# ProProject_PetCareSTM32_MiniSTM32_2024-0.net
KiCad netlist of a schematic drawn in EasyEDA Pro
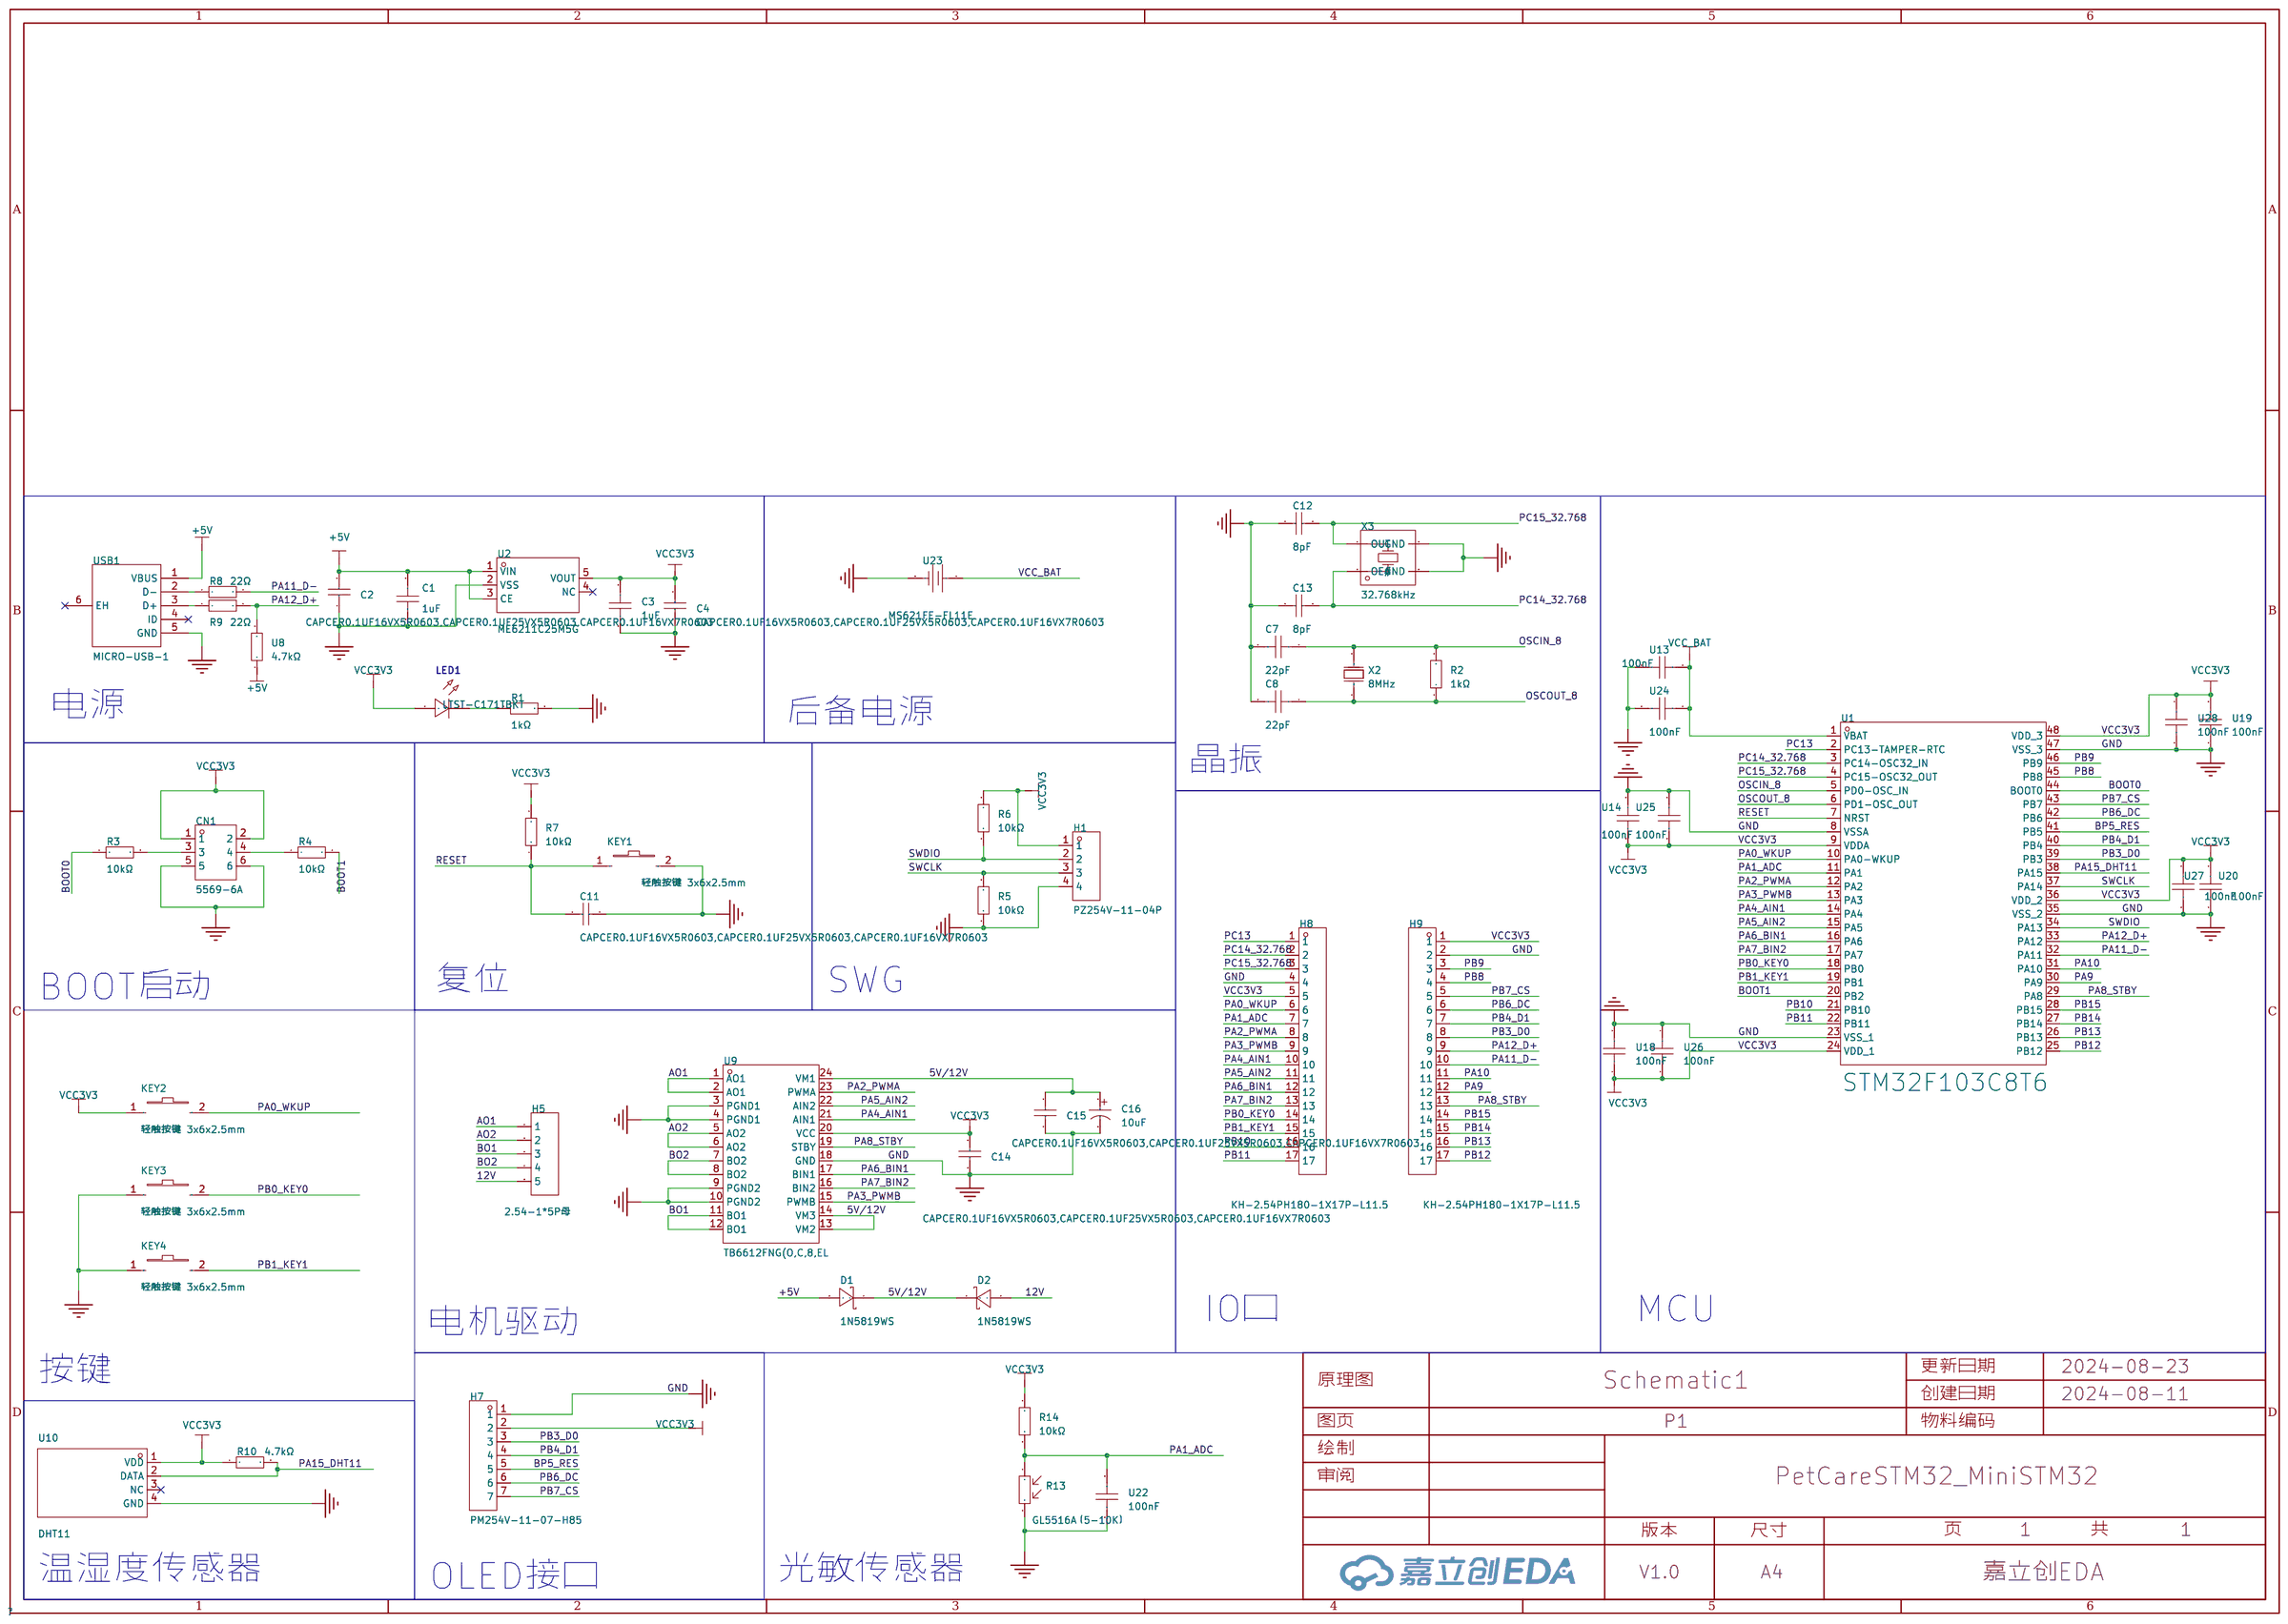
[diagram p0: schematic sheet]

(export (version "E")
  (design (tool "Eeschema 10.0.6"))
  (components
    (comp (ref "C1")
      (value "1uF")
      (footprint "easyedapro:C0603")
      (description "容值:1uF;精度:±10%;额定电压:50V;材质(温度系数):X5R;")
      (fields
        (field (name "Manufacturer Part") "CL10A105KB8NNNC")
        (field (name "Manufacturer") "SAMSUNG(三星)")
      )
      (libsource (lib "easyedapro") (part "CL10A105KB8NNNC"))
    )
    (comp (ref "C2")
      (value "CAPCER0.1UF16VX5R0603,CAPCER0.1UF25VX5R0603,CAPCER0.1UF16VX7R0603")
      (footprint "easyedapro:C0603")
      (libsource (lib "easyedapro") (part "CAPCER0.1UF16VX5R0603,CAPCER0.1UF25VX5R0603,CAPCER0.1UF16VX7R0603"))
    )
    (comp (ref "C3")
      (value "1uF")
      (footprint "easyedapro:C0603")
      (description "容值:1uF;精度:±10%;额定电压:50V;材质(温度系数):X5R;")
      (fields
        (field (name "Manufacturer Part") "CL10A105KB8NNNC")
        (field (name "Manufacturer") "SAMSUNG(三星)")
      )
      (libsource (lib "easyedapro") (part "CL10A105KB8NNNC"))
    )
    (comp (ref "C4")
      (value "CAPCER0.1UF16VX5R0603,CAPCER0.1UF25VX5R0603,CAPCER0.1UF16VX7R0603")
      (footprint "easyedapro:C0603")
      (libsource (lib "easyedapro") (part "CAPCER0.1UF16VX5R0603,CAPCER0.1UF25VX5R0603,CAPCER0.1UF16VX7R0603"))
    )
    (comp (ref "C7")
      (value "22pF")
      (footprint "easyedapro:C0603")
      (description "容值:22pF;精度:±5%;额定电压:50V;材质(温度系数):C0G;")
      (fields
        (field (name "Manufacturer Part") "CL10C220JB81PNC")
        (field (name "Manufacturer") "SAMSUNG(三星)")
      )
      (libsource (lib "easyedapro") (part "CL10C220JB81PNC"))
    )
    (comp (ref "C8")
      (value "22pF")
      (footprint "easyedapro:C0603")
      (description "容值:22pF;精度:±5%;额定电压:50V;材质(温度系数):C0G;")
      (fields
        (field (name "Manufacturer Part") "CL10C220JB81PNC")
        (field (name "Manufacturer") "SAMSUNG(三星)")
      )
      (libsource (lib "easyedapro") (part "CL10C220JB81PNC"))
    )
    (comp (ref "C11")
      (value "CAPCER0.1UF16VX5R0603,CAPCER0.1UF25VX5R0603,CAPCER0.1UF16VX7R0603")
      (footprint "easyedapro:C0603")
      (libsource (lib "easyedapro") (part "CAPCER0.1UF16VX5R0603,CAPCER0.1UF25VX5R0603,CAPCER0.1UF16VX7R0603"))
    )
    (comp (ref "C12")
      (value "8pF")
      (footprint "easyedapro:C0603")
      (description "容值:8pF;额定电压:50V;材质(温度系数):C0G;")
      (fields (field (name "Manufacturer Part") "0603CG8R0C500NT") (field (name "Manufacturer") "FH(风华)"))
      (libsource (lib "easyedapro") (part "0603CG8R0C500NT_C36508"))
    )
    (comp (ref "C13")
      (value "8pF")
      (footprint "easyedapro:C0603")
      (description "容值:8pF;额定电压:50V;材质(温度系数):C0G;")
      (fields (field (name "Manufacturer Part") "0603CG8R0C500NT") (field (name "Manufacturer") "FH(风华)"))
      (libsource (lib "easyedapro") (part "0603CG8R0C500NT_C36508"))
    )
    (comp (ref "C14")
      (value "CAPCER0.1UF16VX5R0603,CAPCER0.1UF25VX5R0603,CAPCER0.1UF16VX7R0603")
      (footprint "easyedapro:C0603")
      (libsource (lib "easyedapro") (part "CAPCER0.1UF16VX5R0603,CAPCER0.1UF25VX5R0603,CAPCER0.1UF16VX7R0603"))
    )
    (comp (ref "C15")
      (value "CAPCER0.1UF16VX5R0603,CAPCER0.1UF25VX5R0603,CAPCER0.1UF16VX7R0603")
      (footprint "easyedapro:C0603")
      (libsource (lib "easyedapro") (part "CAPCER0.1UF16VX5R0603,CAPCER0.1UF25VX5R0603,CAPCER0.1UF16VX7R0603"))
    )
    (comp (ref "C16")
      (value "10uF")
      (footprint "easyedapro:CAP-TH_BD5.0-P2.00-D0.8-FD")
      (description "容值:10uF;精度:±20%;额定电压:25V;")
      (fields (field (name "Manufacturer Part") "KF100M025C110A") (field (name "Manufacturer") "CapXon(丰宾)"))
      (libsource (lib "easyedapro") (part "KF100M025C110A"))
    )
    (comp (ref "CN1")
      (value "5569-6A")
      (footprint "easyedapro:CONN-TH_6P-P4.20_5569-6A-1")
      (libsource (lib "easyedapro") (part "5569-6A"))
    )
    (comp (ref "D1")
      (value "1N5819WS")
      (footprint "easyedapro:SOD-323_L1.8-W1.3-LS2.5-RD")
      (description "正向压降(Vf):600mV@1A;直流反向耐压(Vr):40V;平均整流电流(Io):1A;")
      (fields (field (name "Manufacturer") "Hottech(合科泰)"))
      (libsource (lib "easyedapro") (part "1N5819WS"))
    )
    (comp (ref "D2")
      (value "1N5819WS")
      (footprint "easyedapro:SOD-323_L1.8-W1.3-LS2.5-RD")
      (description "正向压降(Vf):600mV@1A;直流反向耐压(Vr):40V;平均整流电流(Io):1A;")
      (fields (field (name "Manufacturer") "Hottech(合科泰)"))
      (libsource (lib "easyedapro") (part "1N5819WS"))
    )
    (comp (ref "H1")
      (value "PZ254V-11-04P")
      (footprint "easyedapro:HDR-TH_4P-P2.54-V-M")
      (fields (field (name "Manufacturer") "XFCN(兴飞)"))
      (libsource (lib "easyedapro") (part "PZ254V-11-04P_C2691448"))
    )
    (comp (ref "H5")
      (value "2.54-1*5P母")
      (footprint "easyedapro:HDR-TH_5P-P2.54-V-F")
      (description "插孔结构:1x5P;间距:2.54mm;行距:-;安装类型:直插;排数:单排;总孔位数:5P;塑高:-;触头材质:-;触头镀层:-;")
      (fields (field (name "Manufacturer") "BOOMELE(博穆精密)"))
      (libsource (lib "easyedapro") (part "Header-Female-2.54_1x5"))
    )
    (comp (ref "H7")
      (value "PM254V-11-07-H85")
      (footprint "easyedapro:HDR-TH_7P-P2.54-V-F")
      (fields (field (name "Manufacturer") "XFCN(兴飞)"))
      (libsource (lib "easyedapro") (part "PM254V-11-07-H85"))
    )
    (comp (ref "H8")
      (value "KH-2.54PH180-1X17P-L11.5")
      (footprint "easyedapro:HDR-TH_17P-P2.54-V-M")
      (fields (field (name "Manufacturer") "kinghelm(金航标)"))
      (libsource (lib "easyedapro") (part "KH-2.54PH180-1X17P-L11.5"))
    )
    (comp (ref "H9")
      (value "KH-2.54PH180-1X17P-L11.5")
      (footprint "easyedapro:HDR-TH_17P-P2.54-V-M")
      (fields (field (name "Manufacturer") "kinghelm(金航标)"))
      (libsource (lib "easyedapro") (part "KH-2.54PH180-1X17P-L11.5"))
    )
    (comp (ref "KEY1")
      (value "轻触按键 3x6x2.5mm")
      (footprint "easyedapro:SW-SMD_L6.0-W3.6-LS8.0")
      (libsource (lib "easyedapro") (part "3x6x2.5mm"))
    )
    (comp (ref "KEY2")
      (value "轻触按键 3x6x2.5mm")
      (footprint "easyedapro:SW-SMD_L6.0-W3.6-LS8.0")
      (libsource (lib "easyedapro") (part "3x6x2.5mm"))
    )
    (comp (ref "KEY3")
      (value "轻触按键 3x6x2.5mm")
      (footprint "easyedapro:SW-SMD_L6.0-W3.6-LS8.0")
      (libsource (lib "easyedapro") (part "3x6x2.5mm"))
    )
    (comp (ref "KEY4")
      (value "轻触按键 3x6x2.5mm")
      (footprint "easyedapro:SW-SMD_L6.0-W3.6-LS8.0")
      (libsource (lib "easyedapro") (part "3x6x2.5mm"))
    )
    (comp (ref "LED1")
      (value "LTST-C171TBKT")
      (footprint "easyedapro:LED_0805")
      (fields (field (name "Manufacturer") "LITEON(光宝)"))
      (libsource (lib "easyedapro") (part "LED_B"))
    )
    (comp (ref "R1")
      (value "1kΩ")
      (footprint "easyedapro:R0603")
      (description "电阻类型:厚膜电阻;阻值:1kΩ;精度:±1%;功率:100mW;最大工作电压:75V;温度系数:±100ppm/°C;")
      (fields (field (name "Manufacturer Part") "RC0603FR-071KL") (field (name "Manufacturer") "YAGEO(国巨)"))
      (libsource (lib "easyedapro") (part "RC0603FR-071KL"))
    )
    (comp (ref "R2")
      (value "1kΩ")
      (footprint "easyedapro:R0603")
      (description "电阻类型:厚膜电阻;阻值:1kΩ;精度:±0.5%;功率:100mW;最大工作电压:75V;温度系数:±100ppm/°C;")
      (fields
        (field (name "Manufacturer Part") "0603WAD1001T5E")
        (field (name "Manufacturer") "UNI-ROYAL(厚声)")
      )
      (libsource (lib "easyedapro") (part "0603WAD1001T5E"))
    )
    (comp (ref "R3")
      (value "10kΩ")
      (footprint "easyedapro:R0603")
      (description "电阻类型:厚膜电阻;阻值:10kΩ;精度:±1%;功率:100mW;最大工作电压:75V;温度系数:±100ppm/°C;")
      (fields
        (field (name "Manufacturer Part") "0603WAF1002T5E")
        (field (name "Manufacturer") "UNI-ROYAL(厚声)")
      )
      (libsource (lib "easyedapro") (part "0603WAF1002T5E"))
    )
    (comp (ref "R4")
      (value "10kΩ")
      (footprint "easyedapro:R0603")
      (description "电阻类型:厚膜电阻;阻值:10kΩ;精度:±1%;功率:100mW;最大工作电压:75V;温度系数:±100ppm/°C;")
      (fields
        (field (name "Manufacturer Part") "0603WAF1002T5E")
        (field (name "Manufacturer") "UNI-ROYAL(厚声)")
      )
      (libsource (lib "easyedapro") (part "0603WAF1002T5E"))
    )
    (comp (ref "R5")
      (value "10kΩ")
      (footprint "easyedapro:R0603")
      (description "电阻类型:厚膜电阻;阻值:10kΩ;精度:±1%;功率:100mW;最大工作电压:75V;温度系数:±100ppm/°C;")
      (fields
        (field (name "Manufacturer Part") "0603WAF1002T5E")
        (field (name "Manufacturer") "UNI-ROYAL(厚声)")
      )
      (libsource (lib "easyedapro") (part "0603WAF1002T5E"))
    )
    (comp (ref "R6")
      (value "10kΩ")
      (footprint "easyedapro:R0603")
      (description "电阻类型:厚膜电阻;阻值:10kΩ;精度:±1%;功率:100mW;最大工作电压:75V;温度系数:±100ppm/°C;")
      (fields
        (field (name "Manufacturer Part") "0603WAF1002T5E")
        (field (name "Manufacturer") "UNI-ROYAL(厚声)")
      )
      (libsource (lib "easyedapro") (part "0603WAF1002T5E"))
    )
    (comp (ref "R7")
      (value "10kΩ")
      (footprint "easyedapro:R0603")
      (description "电阻类型:厚膜电阻;阻值:10kΩ;精度:±1%;功率:100mW;最大工作电压:75V;温度系数:±100ppm/°C;")
      (fields
        (field (name "Manufacturer Part") "0603WAF1002T5E")
        (field (name "Manufacturer") "UNI-ROYAL(厚声)")
      )
      (libsource (lib "easyedapro") (part "0603WAF1002T5E"))
    )
    (comp (ref "R8")
      (value "22Ω")
      (footprint "easyedapro:R0805")
      (description "电阻类型:薄膜电阻;阻值:22Ω;精度:±1%;功率:250mW;最大工作电压:150V;温度系数:±25ppm/°C;")
      (fields
        (field (name "Manufacturer Part") "TC0525F220JT5E")
        (field (name "Manufacturer") "UNI-ROYAL(厚声)")
      )
      (libsource (lib "easyedapro") (part "TC0525F220JT5E"))
    )
    (comp (ref "R9")
      (value "22Ω")
      (footprint "easyedapro:R0805")
      (description "电阻类型:薄膜电阻;阻值:22Ω;精度:±1%;功率:250mW;最大工作电压:150V;温度系数:±25ppm/°C;")
      (fields
        (field (name "Manufacturer Part") "TC0525F220JT5E")
        (field (name "Manufacturer") "UNI-ROYAL(厚声)")
      )
      (libsource (lib "easyedapro") (part "TC0525F220JT5E"))
    )
    (comp (ref "R10")
      (value "4.7kΩ")
      (footprint "easyedapro:R1206")
      (description "电阻类型:厚膜电阻;阻值:4.7kΩ;精度:±1%;功率:250mW;最大工作电压:200V;温度系数:±100ppm/°C;")
      (fields
        (field (name "Manufacturer Part") "1206W4F4701T5E")
        (field (name "Manufacturer") "UNI-ROYAL(厚声)")
      )
      (libsource (lib "easyedapro") (part "1206W4F4701T5E"))
    )
    (comp (ref "R13")
      (value "GL5516A（5-10K）")
      (footprint "easyedapro:RES-TH_L5.1-W4.3-P3.40_GL55")
      (description "暗电阻:200kΩ;亮电阻 @ 10Lux:5kΩ~10kΩ;光谱峰值(波长):540nm;")
      (fields (field (name "Manufacturer") "JCHL(晶创和立)"))
      (libsource (lib "easyedapro") (part "GL5516A(5-10K)"))
    )
    (comp (ref "R14")
      (value "10kΩ")
      (footprint "easyedapro:R0603")
      (description "电阻类型:厚膜电阻;阻值:10kΩ;精度:±1%;功率:100mW;最大工作电压:75V;温度系数:±100ppm/°C;")
      (fields
        (field (name "Manufacturer Part") "0603WAF1002T5E")
        (field (name "Manufacturer") "UNI-ROYAL(厚声)")
      )
      (libsource (lib "easyedapro") (part "0603WAF1002T5E"))
    )
    (comp (ref "U1")
      (value "STM32F103C8T6")
      (footprint "easyedapro:LQFP-48_L7.0-W7.0-P0.50-LS9.0-BL")
      (description "CPU内核:ARM-M3;程序存储容量:64KB;RAM总容量:20KB;GPIO端口数量:37;工作电压范围:2V~3.6V;CPU最大主频:72MHz;程序存储器类型:FLASH;")
      (fields (field (name "Manufacturer") "ST(意法半导体)"))
      (libsource (lib "easyedapro") (part "STM32F103C8T6"))
    )
    (comp (ref "U2")
      (value "ME6211C25M5G")
      (footprint "easyedapro:SOT-23-5_L2.9-W1.7-P0.95-LS2.8-BL")
      (fields (field (name "Manufacturer") "MICRONE(南京微盟)"))
      (libsource (lib "easyedapro") (part "ME6211C25M5G"))
    )
    (comp (ref "U8")
      (value "4.7kΩ")
      (footprint "easyedapro:R0603")
      (description "电阻类型:薄膜电阻;阻值:4.7kΩ;精度:±1%;功率:100mW;最大工作电压:75V;温度系数:±50ppm/°C;")
      (fields (field (name "Manufacturer Part") "AR03FTDX4701A") (field (name "Manufacturer") "Viking(光颉)"))
      (libsource (lib "easyedapro") (part "AR03FTDX4701A"))
    )
    (comp (ref "U9")
      (value "TB6612FNG(O,C,8,EL")
      (footprint "easyedapro:SSOP-24_L8.4-W5.8-P0.65-LS7.8-BL")
      (description "双直流电机驱动器集成电路")
      (fields (field (name "Manufacturer") "TOSHIBA(东芝)"))
      (libsource (lib "easyedapro") (part "TB6612FNG(O,C,8,EL"))
    )
    (comp (ref "U10")
      (value "DHT11")
      (footprint "easyedapro:SENSOR-TH_DHT11")
      (description "新款电容式数字温湿度传感器,老款已停产16.1x12.6x5.8mm")
      (fields (field (name "Manufacturer") "广州奥松"))
      (libsource (lib "easyedapro") (part "DHT11"))
    )
    (comp (ref "U13")
      (value "100nF")
      (footprint "easyedapro:C0603")
      (description "容值:100nF;精度:±10%;额定电压:50V;材质(温度系数):X7R;")
      (fields
        (field (name "Manufacturer Part") "CGA0603X7R104K500JT")
        (field (name "Manufacturer") "HRE(芯声)")
      )
      (libsource (lib "easyedapro") (part "CGA0603X7R104K500JT"))
    )
    (comp (ref "U14")
      (value "100nF")
      (footprint "easyedapro:C0603")
      (description "容值:100nF;精度:±10%;额定电压:50V;材质(温度系数):X7R;")
      (fields
        (field (name "Manufacturer Part") "CGA0603X7R104K500JT")
        (field (name "Manufacturer") "HRE(芯声)")
      )
      (libsource (lib "easyedapro") (part "CGA0603X7R104K500JT"))
    )
    (comp (ref "U18")
      (value "100nF")
      (footprint "easyedapro:C0603")
      (description "容值:100nF;精度:±10%;额定电压:50V;材质(温度系数):X7R;")
      (fields
        (field (name "Manufacturer Part") "CGA0603X7R104K500JT")
        (field (name "Manufacturer") "HRE(芯声)")
      )
      (libsource (lib "easyedapro") (part "CGA0603X7R104K500JT"))
    )
    (comp (ref "U19")
      (value "100nF")
      (footprint "easyedapro:C0603")
      (description "容值:100nF;精度:±10%;额定电压:50V;材质(温度系数):X7R;")
      (fields
        (field (name "Manufacturer Part") "CGA0603X7R104K500JT")
        (field (name "Manufacturer") "HRE(芯声)")
      )
      (libsource (lib "easyedapro") (part "CGA0603X7R104K500JT"))
    )
    (comp (ref "U20")
      (value "100nF")
      (footprint "easyedapro:C0603")
      (description "容值:100nF;精度:±10%;额定电压:50V;材质(温度系数):X7R;")
      (fields
        (field (name "Manufacturer Part") "CGA0603X7R104K500JT")
        (field (name "Manufacturer") "HRE(芯声)")
      )
      (libsource (lib "easyedapro") (part "CGA0603X7R104K500JT"))
    )
    (comp (ref "U22")
      (value "100nF")
      (footprint "easyedapro:C0603")
      (description "容值:100nF;精度:±10%;额定电压:50V;材质(温度系数):X7R;")
      (fields
        (field (name "Manufacturer Part") "CGA0603X7R104K500JT")
        (field (name "Manufacturer") "HRE(芯声)")
      )
      (libsource (lib "easyedapro") (part "CGA0603X7R104K500JT"))
    )
    (comp (ref "U23")
      (value "MS621FE-FL11E")
      (footprint "easyedapro:BAT-SMD_FL11E")
      (description "FL11E 3.3V可充电纽扣电池 5.5mAH")
      (fields (field (name "Manufacturer") "Seiko(精工)"))
      (libsource (lib "easyedapro") (part "MS621FE-FL11E"))
    )
    (comp (ref "U24")
      (value "100nF")
      (footprint "easyedapro:C0603")
      (description "容值:100nF;精度:±10%;额定电压:50V;材质(温度系数):X7R;")
      (fields
        (field (name "Manufacturer Part") "CGA0603X7R104K500JT")
        (field (name "Manufacturer") "HRE(芯声)")
      )
      (libsource (lib "easyedapro") (part "CGA0603X7R104K500JT"))
    )
    (comp (ref "U25")
      (value "100nF")
      (footprint "easyedapro:C0603")
      (description "容值:100nF;精度:±10%;额定电压:50V;材质(温度系数):X7R;")
      (fields
        (field (name "Manufacturer Part") "CGA0603X7R104K500JT")
        (field (name "Manufacturer") "HRE(芯声)")
      )
      (libsource (lib "easyedapro") (part "CGA0603X7R104K500JT"))
    )
    (comp (ref "U26")
      (value "100nF")
      (footprint "easyedapro:C0603")
      (description "容值:100nF;精度:±10%;额定电压:50V;材质(温度系数):X7R;")
      (fields
        (field (name "Manufacturer Part") "CGA0603X7R104K500JT")
        (field (name "Manufacturer") "HRE(芯声)")
      )
      (libsource (lib "easyedapro") (part "CGA0603X7R104K500JT"))
    )
    (comp (ref "U27")
      (value "100nF")
      (footprint "easyedapro:C0603")
      (description "容值:100nF;精度:±10%;额定电压:50V;材质(温度系数):X7R;")
      (fields
        (field (name "Manufacturer Part") "CGA0603X7R104K500JT")
        (field (name "Manufacturer") "HRE(芯声)")
      )
      (libsource (lib "easyedapro") (part "CGA0603X7R104K500JT"))
    )
    (comp (ref "U28")
      (value "100nF")
      (footprint "easyedapro:C0603")
      (description "容值:100nF;精度:±10%;额定电压:50V;材质(温度系数):X7R;")
      (fields
        (field (name "Manufacturer Part") "CGA0603X7R104K500JT")
        (field (name "Manufacturer") "HRE(芯声)")
      )
      (libsource (lib "easyedapro") (part "CGA0603X7R104K500JT"))
    )
    (comp (ref "USB1")
      (value "MICRO-USB-1")
      (footprint "easyedapro:MICRO-USB-SMD_C9900008946")
      (libsource (lib "easyedapro") (part "MICRO-USB-1"))
    )
    (comp (ref "X2")
      (value "8MHz")
      (footprint "easyedapro:OSC-SMD_L5.0-W3.2")
      (description "晶振类型:贴片晶振;频率:8MHz;常温频差:±20ppm;外接负载电容:18pF;频率稳定度(全温):±30ppm;")
      (fields
        (field (name "Manufacturer Part") "ABM3-8.000MHZ-D2Y-T")
        (field (name "Manufacturer") "ABRACON")
      )
      (libsource (lib "easyedapro") (part "ABM3-8.000MHZ-D2Y-T"))
    )
    (comp (ref "X3")
      (value "32.768kHz")
      (footprint "easyedapro:CRYSTAL-SMD_4P-L8.0-W3.8-BL")
      (description "晶振类型:-;频率:32.768kHz;常温频差:±20ppm;外接负载电容:12.5pF;频率稳定度(全温):-;")
      (fields (field (name "Manufacturer Part") "ABS25-32.768KHZ-T") (field (name "Manufacturer") "ABRACON"))
      (libsource (lib "easyedapro") (part "ABS25-32.768KHZ-T"))
    )
  )
  (nets
    (net (code "1") (name "+5V") (class "Default")
      (node (ref "C1") (pin "2") (pinfunction "2_2") (pintype "unspecified"))
      (node (ref "C2") (pin "2") (pinfunction "2_2") (pintype "input"))
      (node (ref "D1") (pin "2") (pinfunction "A_2") (pintype "unspecified"))
      (node (ref "U2") (pin "1") (pinfunction "VIN_1") (pintype "unspecified"))
      (node (ref "U2") (pin "3") (pinfunction "CE_3") (pintype "unspecified"))
      (node (ref "U8") (pin "1") (pinfunction "1_1") (pintype "unspecified"))
      (node (ref "USB1") (pin "1") (pinfunction "VBUS_1") (pintype "input"))
    )
    (net (code "2") (name "/5V{slash}12V") (class "Default")
      (node (ref "C15") (pin "2") (pinfunction "2_2") (pintype "input"))
      (node (ref "C16") (pin "1") (pinfunction "1_1") (pintype "input"))
      (node (ref "D1") (pin "1") (pinfunction "K_1") (pintype "unspecified"))
      (node (ref "D2") (pin "1") (pinfunction "K_1") (pintype "unspecified"))
      (node (ref "U9") (pin "13") (pinfunction "VM2_13") (pintype "unspecified"))
      (node (ref "U9") (pin "14") (pinfunction "VM3_14") (pintype "unspecified"))
      (node (ref "U9") (pin "24") (pinfunction "VM1_24") (pintype "unspecified"))
    )
    (net (code "3") (name "/12V") (class "Default")
      (node (ref "D2") (pin "2") (pinfunction "A_2") (pintype "unspecified"))
      (node (ref "H5") (pin "5") (pinfunction "5_5") (pintype "input"))
    )
    (net (code "4") (name "/AO1") (class "Default")
      (node (ref "H5") (pin "1") (pinfunction "1_1") (pintype "input"))
      (node (ref "U9") (pin "1") (pinfunction "AO1_1") (pintype "unspecified"))
      (node (ref "U9") (pin "2") (pinfunction "AO1_2") (pintype "unspecified"))
    )
    (net (code "5") (name "/AO2") (class "Default")
      (node (ref "H5") (pin "2") (pinfunction "2_2") (pintype "input"))
      (node (ref "U9") (pin "5") (pinfunction "AO2_5") (pintype "unspecified"))
      (node (ref "U9") (pin "6") (pinfunction "AO2_6") (pintype "unspecified"))
    )
    (net (code "6") (name "/BO1") (class "Default")
      (node (ref "H5") (pin "3") (pinfunction "3_3") (pintype "input"))
      (node (ref "U9") (pin "11") (pinfunction "BO1_11") (pintype "unspecified"))
      (node (ref "U9") (pin "12") (pinfunction "BO1_12") (pintype "unspecified"))
    )
    (net (code "7") (name "/BO2") (class "Default")
      (node (ref "H5") (pin "4") (pinfunction "4_4") (pintype "input"))
      (node (ref "U9") (pin "7") (pinfunction "BO2_7") (pintype "unspecified"))
      (node (ref "U9") (pin "8") (pinfunction "BO2_8") (pintype "unspecified"))
    )
    (net (code "8") (name "/BOOT0") (class "Default")
      (node (ref "R3") (pin "1") (pinfunction "1_1") (pintype "input"))
      (node (ref "U1") (pin "44") (pinfunction "BOOT0_44") (pintype "unspecified"))
    )
    (net (code "9") (name "/BOOT1") (class "Default")
      (node (ref "R4") (pin "2") (pinfunction "2_2") (pintype "input"))
      (node (ref "U1") (pin "20") (pinfunction "PB2_20") (pintype "unspecified"))
    )
    (net (code "10") (name "/BP5_RES") (class "Default")
      (node (ref "H7") (pin "5") (pinfunction "5_5") (pintype "unspecified"))
      (node (ref "U1") (pin "41") (pinfunction "PB5_41") (pintype "unspecified"))
    )
    (net (code "11") (name "/OSCIN_8") (class "Default")
      (node (ref "C7") (pin "1") (pinfunction "1_1") (pintype "unspecified"))
      (node (ref "R2") (pin "2") (pinfunction "2_2") (pintype "input"))
      (node (ref "U1") (pin "5") (pinfunction "PD0-OSC_IN_5") (pintype "unspecified"))
      (node (ref "X2") (pin "2") (pinfunction "OSC2_2") (pintype "input"))
    )
    (net (code "12") (name "/OSCOUT_8") (class "Default")
      (node (ref "C8") (pin "1") (pinfunction "1_1") (pintype "unspecified"))
      (node (ref "R2") (pin "1") (pinfunction "1_1") (pintype "input"))
      (node (ref "U1") (pin "6") (pinfunction "PD1-OSC_OUT_6") (pintype "unspecified"))
      (node (ref "X2") (pin "1") (pinfunction "OSC1_1") (pintype "input"))
    )
    (net (code "13") (name "/PA0_WKUP") (class "Default")
      (node (ref "H8") (pin "6") (pinfunction "6_6") (pintype "unspecified"))
      (node (ref "KEY2") (pin "2") (pinfunction "2_2") (pintype "input"))
      (node (ref "U1") (pin "10") (pinfunction "PA0-WKUP_10") (pintype "unspecified"))
    )
    (net (code "14") (name "/PA1_ADC") (class "Default")
      (node (ref "H8") (pin "7") (pinfunction "7_7") (pintype "unspecified"))
      (node (ref "R13") (pin "1") (pinfunction "1_1") (pintype "input"))
      (node (ref "R14") (pin "1") (pinfunction "1_1") (pintype "input"))
      (node (ref "U1") (pin "11") (pinfunction "PA1_11") (pintype "unspecified"))
      (node (ref "U22") (pin "2") (pinfunction "2_2") (pintype "unspecified"))
    )
    (net (code "15") (name "/PA2_PWMA") (class "Default")
      (node (ref "H8") (pin "8") (pinfunction "8_8") (pintype "unspecified"))
      (node (ref "U1") (pin "12") (pinfunction "PA2_12") (pintype "unspecified"))
      (node (ref "U9") (pin "23") (pinfunction "PWMA_23") (pintype "unspecified"))
    )
    (net (code "16") (name "/PA3_PWMB") (class "Default")
      (node (ref "H8") (pin "9") (pinfunction "9_9") (pintype "unspecified"))
      (node (ref "U1") (pin "13") (pinfunction "PA3_13") (pintype "unspecified"))
      (node (ref "U9") (pin "15") (pinfunction "PWMB_15") (pintype "unspecified"))
    )
    (net (code "17") (name "/PA4_AIN1") (class "Default")
      (node (ref "H8") (pin "10") (pinfunction "10_10") (pintype "unspecified"))
      (node (ref "U1") (pin "14") (pinfunction "PA4_14") (pintype "unspecified"))
      (node (ref "U9") (pin "21") (pinfunction "AIN1_21") (pintype "unspecified"))
    )
    (net (code "18") (name "/PA5_AIN2") (class "Default")
      (node (ref "H8") (pin "11") (pinfunction "11_11") (pintype "unspecified"))
      (node (ref "U1") (pin "15") (pinfunction "PA5_15") (pintype "unspecified"))
      (node (ref "U9") (pin "22") (pinfunction "AIN2_22") (pintype "unspecified"))
    )
    (net (code "19") (name "/PA6_BIN1") (class "Default")
      (node (ref "H8") (pin "12") (pinfunction "12_12") (pintype "unspecified"))
      (node (ref "U1") (pin "16") (pinfunction "PA6_16") (pintype "unspecified"))
      (node (ref "U9") (pin "17") (pinfunction "BIN1_17") (pintype "unspecified"))
    )
    (net (code "20") (name "/PA7_BIN2") (class "Default")
      (node (ref "H8") (pin "13") (pinfunction "13_13") (pintype "unspecified"))
      (node (ref "U1") (pin "17") (pinfunction "PA7_17") (pintype "unspecified"))
      (node (ref "U9") (pin "16") (pinfunction "BIN2_16") (pintype "unspecified"))
    )
    (net (code "21") (name "/PA8_STBY") (class "Default")
      (node (ref "H9") (pin "13") (pinfunction "13_13") (pintype "unspecified"))
      (node (ref "U1") (pin "29") (pinfunction "PA8_29") (pintype "unspecified"))
      (node (ref "U9") (pin "19") (pinfunction "STBY_19") (pintype "unspecified"))
    )
    (net (code "22") (name "/PA9") (class "Default")
      (node (ref "H9") (pin "12") (pinfunction "12_12") (pintype "unspecified"))
      (node (ref "U1") (pin "30") (pinfunction "PA9_30") (pintype "unspecified"))
    )
    (net (code "23") (name "/PA10") (class "Default")
      (node (ref "H9") (pin "11") (pinfunction "11_11") (pintype "unspecified"))
      (node (ref "U1") (pin "31") (pinfunction "PA10_31") (pintype "unspecified"))
    )
    (net (code "24") (name "/PA11_D-") (class "Default")
      (node (ref "H9") (pin "10") (pinfunction "10_10") (pintype "unspecified"))
      (node (ref "R8") (pin "2") (pinfunction "2_2") (pintype "input"))
      (node (ref "U1") (pin "32") (pinfunction "PA11_32") (pintype "unspecified"))
    )
    (net (code "25") (name "/PA12_D+") (class "Default")
      (node (ref "H9") (pin "9") (pinfunction "9_9") (pintype "unspecified"))
      (node (ref "R9") (pin "2") (pinfunction "2_2") (pintype "input"))
      (node (ref "U1") (pin "33") (pinfunction "PA12_33") (pintype "unspecified"))
      (node (ref "U8") (pin "2") (pinfunction "2_2") (pintype "unspecified"))
    )
    (net (code "26") (name "/PA15_DHT11") (class "Default")
      (node (ref "R10") (pin "2") (pinfunction "2_2") (pintype "input"))
      (node (ref "U1") (pin "38") (pinfunction "PA15_38") (pintype "unspecified"))
      (node (ref "U10") (pin "2") (pinfunction "DATA_2") (pintype "unspecified"))
    )
    (net (code "27") (name "/PB0_KEY0") (class "Default")
      (node (ref "H8") (pin "14") (pinfunction "14_14") (pintype "unspecified"))
      (node (ref "KEY3") (pin "2") (pinfunction "2_2") (pintype "input"))
      (node (ref "U1") (pin "18") (pinfunction "PB0_18") (pintype "unspecified"))
    )
    (net (code "28") (name "/PB1_KEY1") (class "Default")
      (node (ref "H8") (pin "15") (pinfunction "15_15") (pintype "unspecified"))
      (node (ref "KEY4") (pin "2") (pinfunction "2_2") (pintype "input"))
      (node (ref "U1") (pin "19") (pinfunction "PB1_19") (pintype "unspecified"))
    )
    (net (code "29") (name "/PB3_D0") (class "Default")
      (node (ref "H7") (pin "3") (pinfunction "3_3") (pintype "unspecified"))
      (node (ref "H9") (pin "8") (pinfunction "8_8") (pintype "unspecified"))
      (node (ref "U1") (pin "39") (pinfunction "PB3_39") (pintype "unspecified"))
    )
    (net (code "30") (name "/PB4_D1") (class "Default")
      (node (ref "H7") (pin "4") (pinfunction "4_4") (pintype "unspecified"))
      (node (ref "H9") (pin "7") (pinfunction "7_7") (pintype "unspecified"))
      (node (ref "U1") (pin "40") (pinfunction "PB4_40") (pintype "unspecified"))
    )
    (net (code "31") (name "/PB6_DC") (class "Default")
      (node (ref "H7") (pin "6") (pinfunction "6_6") (pintype "unspecified"))
      (node (ref "H9") (pin "6") (pinfunction "6_6") (pintype "unspecified"))
      (node (ref "U1") (pin "42") (pinfunction "PB6_42") (pintype "unspecified"))
    )
    (net (code "32") (name "/PB7_CS") (class "Default")
      (node (ref "H7") (pin "7") (pinfunction "7_7") (pintype "unspecified"))
      (node (ref "H9") (pin "5") (pinfunction "5_5") (pintype "unspecified"))
      (node (ref "U1") (pin "43") (pinfunction "PB7_43") (pintype "unspecified"))
    )
    (net (code "33") (name "/PB8") (class "Default")
      (node (ref "H9") (pin "4") (pinfunction "4_4") (pintype "unspecified"))
      (node (ref "U1") (pin "45") (pinfunction "PB8_45") (pintype "unspecified"))
    )
    (net (code "34") (name "/PB9") (class "Default")
      (node (ref "H9") (pin "3") (pinfunction "3_3") (pintype "unspecified"))
      (node (ref "U1") (pin "46") (pinfunction "PB9_46") (pintype "unspecified"))
    )
    (net (code "35") (name "/PB10") (class "Default")
      (node (ref "H8") (pin "16") (pinfunction "16_16") (pintype "unspecified"))
      (node (ref "U1") (pin "21") (pinfunction "PB10_21") (pintype "unspecified"))
    )
    (net (code "36") (name "/PB11") (class "Default")
      (node (ref "H8") (pin "17") (pinfunction "17_17") (pintype "unspecified"))
      (node (ref "U1") (pin "22") (pinfunction "PB11_22") (pintype "unspecified"))
    )
    (net (code "37") (name "/PB12") (class "Default")
      (node (ref "H9") (pin "17") (pinfunction "17_17") (pintype "unspecified"))
      (node (ref "U1") (pin "25") (pinfunction "PB12_25") (pintype "unspecified"))
    )
    (net (code "38") (name "/PB13") (class "Default")
      (node (ref "H9") (pin "16") (pinfunction "16_16") (pintype "unspecified"))
      (node (ref "U1") (pin "26") (pinfunction "PB13_26") (pintype "unspecified"))
    )
    (net (code "39") (name "/PB14") (class "Default")
      (node (ref "H9") (pin "15") (pinfunction "15_15") (pintype "unspecified"))
      (node (ref "U1") (pin "27") (pinfunction "PB14_27") (pintype "unspecified"))
    )
    (net (code "40") (name "/PB15") (class "Default")
      (node (ref "H9") (pin "14") (pinfunction "14_14") (pintype "unspecified"))
      (node (ref "U1") (pin "28") (pinfunction "PB15_28") (pintype "unspecified"))
    )
    (net (code "41") (name "/PC13") (class "Default")
      (node (ref "H8") (pin "1") (pinfunction "1_1") (pintype "unspecified"))
      (node (ref "U1") (pin "2") (pinfunction "PC13-TAMPER-RTC_2") (pintype "unspecified"))
    )
    (net (code "42") (name "/PC14_32.768") (class "Default")
      (node (ref "C13") (pin "2") (pinfunction "2_2") (pintype "input"))
      (node (ref "H8") (pin "2") (pinfunction "2_2") (pintype "unspecified"))
      (node (ref "U1") (pin "3") (pinfunction "PC14-OSC32_IN_3") (pintype "unspecified"))
      (node (ref "X3") (pin "1") (pinfunction "OE#_1") (pintype "input"))
    )
    (net (code "43") (name "/PC15_32.768") (class "Default")
      (node (ref "C12") (pin "2") (pinfunction "2_2") (pintype "input"))
      (node (ref "H8") (pin "3") (pinfunction "3_3") (pintype "unspecified"))
      (node (ref "U1") (pin "4") (pinfunction "PC15-OSC32_OUT_4") (pintype "unspecified"))
      (node (ref "X3") (pin "4") (pinfunction "OUT_4") (pintype "input"))
    )
    (net (code "44") (name "/RESET") (class "Default")
      (node (ref "C11") (pin "1") (pinfunction "1_1") (pintype "input"))
      (node (ref "KEY1") (pin "1") (pinfunction "1_1") (pintype "input"))
      (node (ref "R7") (pin "1") (pinfunction "1_1") (pintype "input"))
      (node (ref "U1") (pin "7") (pinfunction "NRST_7") (pintype "unspecified"))
    )
    (net (code "45") (name "/SWCLK") (class "Default")
      (node (ref "H1") (pin "3") (pinfunction "3_3") (pintype "unspecified"))
      (node (ref "R5") (pin "2") (pinfunction "2_2") (pintype "input"))
      (node (ref "U1") (pin "37") (pinfunction "PA14_37") (pintype "unspecified"))
    )
    (net (code "46") (name "/SWDIO") (class "Default")
      (node (ref "H1") (pin "2") (pinfunction "2_2") (pintype "unspecified"))
      (node (ref "R6") (pin "1") (pinfunction "1_1") (pintype "input"))
      (node (ref "U1") (pin "34") (pinfunction "PA13_34") (pintype "unspecified"))
    )
    (net (code "47") (name "GND") (class "Default")
      (node (ref "C1") (pin "1") (pinfunction "1_1") (pintype "unspecified"))
      (node (ref "C11") (pin "2") (pinfunction "2_2") (pintype "input"))
      (node (ref "C12") (pin "1") (pinfunction "1_1") (pintype "input"))
      (node (ref "C13") (pin "1") (pinfunction "1_1") (pintype "input"))
      (node (ref "C14") (pin "1") (pinfunction "1_1") (pintype "input"))
      (node (ref "C15") (pin "1") (pinfunction "1_1") (pintype "input"))
      (node (ref "C16") (pin "2") (pinfunction "2_2") (pintype "input"))
      (node (ref "C2") (pin "1") (pinfunction "1_1") (pintype "input"))
      (node (ref "C3") (pin "1") (pinfunction "1_1") (pintype "unspecified"))
      (node (ref "C4") (pin "1") (pinfunction "1_1") (pintype "input"))
      (node (ref "C7") (pin "2") (pinfunction "2_2") (pintype "unspecified"))
      (node (ref "C8") (pin "2") (pinfunction "2_2") (pintype "unspecified"))
      (node (ref "CN1") (pin "5") (pinfunction "5_5") (pintype "unspecified"))
      (node (ref "CN1") (pin "6") (pinfunction "6_6") (pintype "unspecified"))
      (node (ref "H1") (pin "4") (pinfunction "4_4") (pintype "unspecified"))
      (node (ref "H7") (pin "1") (pinfunction "1_1") (pintype "unspecified"))
      (node (ref "H8") (pin "4") (pinfunction "4_4") (pintype "unspecified"))
      (node (ref "H9") (pin "2") (pinfunction "2_2") (pintype "unspecified"))
      (node (ref "KEY1") (pin "2") (pinfunction "2_2") (pintype "input"))
      (node (ref "KEY3") (pin "1") (pinfunction "1_1") (pintype "input"))
      (node (ref "KEY4") (pin "1") (pinfunction "1_1") (pintype "input"))
      (node (ref "R1") (pin "2") (pinfunction "2_2") (pintype "input"))
      (node (ref "R13") (pin "2") (pinfunction "2_2") (pintype "input"))
      (node (ref "R5") (pin "1") (pinfunction "1_1") (pintype "input"))
      (node (ref "U1") (pin "23") (pinfunction "VSS_1_23") (pintype "unspecified"))
      (node (ref "U1") (pin "35") (pinfunction "VSS_2_35") (pintype "unspecified"))
      (node (ref "U1") (pin "47") (pinfunction "VSS_3_47") (pintype "unspecified"))
      (node (ref "U1") (pin "8") (pinfunction "VSSA_8") (pintype "unspecified"))
      (node (ref "U10") (pin "4") (pinfunction "GND_4") (pintype "unspecified"))
      (node (ref "U13") (pin "2") (pinfunction "2_2") (pintype "unspecified"))
      (node (ref "U14") (pin "2") (pinfunction "2_2") (pintype "unspecified"))
      (node (ref "U18") (pin "2") (pinfunction "2_2") (pintype "unspecified"))
      (node (ref "U19") (pin "1") (pinfunction "1_1") (pintype "unspecified"))
      (node (ref "U2") (pin "2") (pinfunction "VSS_2") (pintype "unspecified"))
      (node (ref "U20") (pin "1") (pinfunction "1_1") (pintype "unspecified"))
      (node (ref "U22") (pin "1") (pinfunction "1_1") (pintype "unspecified"))
      (node (ref "U23") (pin "2") (pinfunction "-_2") (pintype "unspecified"))
      (node (ref "U24") (pin "2") (pinfunction "2_2") (pintype "unspecified"))
      (node (ref "U25") (pin "1") (pinfunction "1_1") (pintype "unspecified"))
      (node (ref "U26") (pin "1") (pinfunction "1_1") (pintype "unspecified"))
      (node (ref "U27") (pin "2") (pinfunction "2_2") (pintype "unspecified"))
      (node (ref "U28") (pin "2") (pinfunction "2_2") (pintype "unspecified"))
      (node (ref "U9") (pin "10") (pinfunction "PGND2_10") (pintype "unspecified"))
      (node (ref "U9") (pin "18") (pinfunction "GND_18") (pintype "unspecified"))
      (node (ref "U9") (pin "3") (pinfunction "PGND1_3") (pintype "unspecified"))
      (node (ref "U9") (pin "4") (pinfunction "PGND1_4") (pintype "unspecified"))
      (node (ref "U9") (pin "9") (pinfunction "PGND2_9") (pintype "unspecified"))
      (node (ref "USB1") (pin "5") (pinfunction "GND_5") (pintype "input"))
      (node (ref "X3") (pin "2") (pinfunction "GND_2") (pintype "input"))
      (node (ref "X3") (pin "3") (pinfunction "GND_3") (pintype "input"))
    )
    (net (code "48") (name "Net-(CN1-Pad3)") (class "Default")
      (node (ref "CN1") (pin "3") (pinfunction "3_3") (pintype "unspecified"))
      (node (ref "R3") (pin "2") (pinfunction "2_2") (pintype "input"))
    )
    (net (code "49") (name "Net-(CN1-Pad4)") (class "Default")
      (node (ref "CN1") (pin "4") (pinfunction "4_4") (pintype "unspecified"))
      (node (ref "R4") (pin "1") (pinfunction "1_1") (pintype "input"))
    )
    (net (code "50") (name "Net-(LED1-C)") (class "Default")
      (node (ref "LED1") (pin "1") (pinfunction "C_1") (pintype "input"))
      (node (ref "R1") (pin "1") (pinfunction "1_1") (pintype "input"))
    )
    (net (code "51") (name "Net-(USB1-D+)") (class "Default")
      (node (ref "R9") (pin "1") (pinfunction "1_1") (pintype "input"))
      (node (ref "USB1") (pin "3") (pinfunction "D+_3") (pintype "input"))
    )
    (net (code "52") (name "Net-(USB1-D-)") (class "Default")
      (node (ref "R8") (pin "1") (pinfunction "1_1") (pintype "input"))
      (node (ref "USB1") (pin "2") (pinfunction "D-_2") (pintype "input"))
    )
    (net (code "53") (name "VCC3V3") (class "Default")
      (node (ref "C14") (pin "2") (pinfunction "2_2") (pintype "input"))
      (node (ref "C3") (pin "2") (pinfunction "2_2") (pintype "unspecified"))
      (node (ref "C4") (pin "2") (pinfunction "2_2") (pintype "input"))
      (node (ref "CN1") (pin "1") (pinfunction "1_1") (pintype "unspecified"))
      (node (ref "CN1") (pin "2") (pinfunction "2_2") (pintype "unspecified"))
      (node (ref "H1") (pin "1") (pinfunction "1_1") (pintype "unspecified"))
      (node (ref "H7") (pin "2") (pinfunction "2_2") (pintype "unspecified"))
      (node (ref "H8") (pin "5") (pinfunction "5_5") (pintype "unspecified"))
      (node (ref "H9") (pin "1") (pinfunction "1_1") (pintype "unspecified"))
      (node (ref "KEY2") (pin "1") (pinfunction "1_1") (pintype "input"))
      (node (ref "LED1") (pin "2") (pinfunction "A_2") (pintype "input"))
      (node (ref "R10") (pin "1") (pinfunction "1_1") (pintype "input"))
      (node (ref "R14") (pin "2") (pinfunction "2_2") (pintype "input"))
      (node (ref "R6") (pin "2") (pinfunction "2_2") (pintype "input"))
      (node (ref "R7") (pin "2") (pinfunction "2_2") (pintype "input"))
      (node (ref "U1") (pin "24") (pinfunction "VDD_1_24") (pintype "unspecified"))
      (node (ref "U1") (pin "36") (pinfunction "VDD_2_36") (pintype "unspecified"))
      (node (ref "U1") (pin "48") (pinfunction "VDD_3_48") (pintype "unspecified"))
      (node (ref "U1") (pin "9") (pinfunction "VDDA_9") (pintype "unspecified"))
      (node (ref "U10") (pin "1") (pinfunction "VDD_1") (pintype "unspecified"))
      (node (ref "U14") (pin "1") (pinfunction "1_1") (pintype "unspecified"))
      (node (ref "U18") (pin "1") (pinfunction "1_1") (pintype "unspecified"))
      (node (ref "U19") (pin "2") (pinfunction "2_2") (pintype "unspecified"))
      (node (ref "U2") (pin "5") (pinfunction "VOUT_5") (pintype "unspecified"))
      (node (ref "U20") (pin "2") (pinfunction "2_2") (pintype "unspecified"))
      (node (ref "U25") (pin "2") (pinfunction "2_2") (pintype "unspecified"))
      (node (ref "U26") (pin "2") (pinfunction "2_2") (pintype "unspecified"))
      (node (ref "U27") (pin "1") (pinfunction "1_1") (pintype "unspecified"))
      (node (ref "U28") (pin "1") (pinfunction "1_1") (pintype "unspecified"))
      (node (ref "U9") (pin "20") (pinfunction "VCC_20") (pintype "unspecified"))
    )
    (net (code "54") (name "VCC_BAT") (class "Default")
      (node (ref "U1") (pin "1") (pinfunction "VBAT_1") (pintype "unspecified"))
      (node (ref "U13") (pin "1") (pinfunction "1_1") (pintype "unspecified"))
      (node (ref "U23") (pin "1") (pinfunction "+_1") (pintype "unspecified"))
      (node (ref "U24") (pin "1") (pinfunction "1_1") (pintype "unspecified"))
    )
    (net (code "55") (name "unconnected-(U2-NC-Pad4)") (class "Default")
      (node (ref "U2") (pin "4") (pinfunction "NC_4") (pintype "unspecified+no_connect"))
    )
    (net (code "56") (name "unconnected-(U10-NC-Pad3)") (class "Default")
      (node (ref "U10") (pin "3") (pinfunction "NC_3") (pintype "unspecified+no_connect"))
    )
    (net (code "57") (name "unconnected-(USB1-EH-Pad6)") (class "Default")
      (node (ref "USB1") (pin "6") (pinfunction "EH_6") (pintype "input+no_connect"))
    )
    (net (code "58") (name "unconnected-(USB1-ID-Pad4)") (class "Default")
      (node (ref "USB1") (pin "4") (pinfunction "ID_4") (pintype "input+no_connect"))
    )
  )
)
